# Interface_-_RS485.net
KiCad netlist of a schematic drawn in Altium Designer
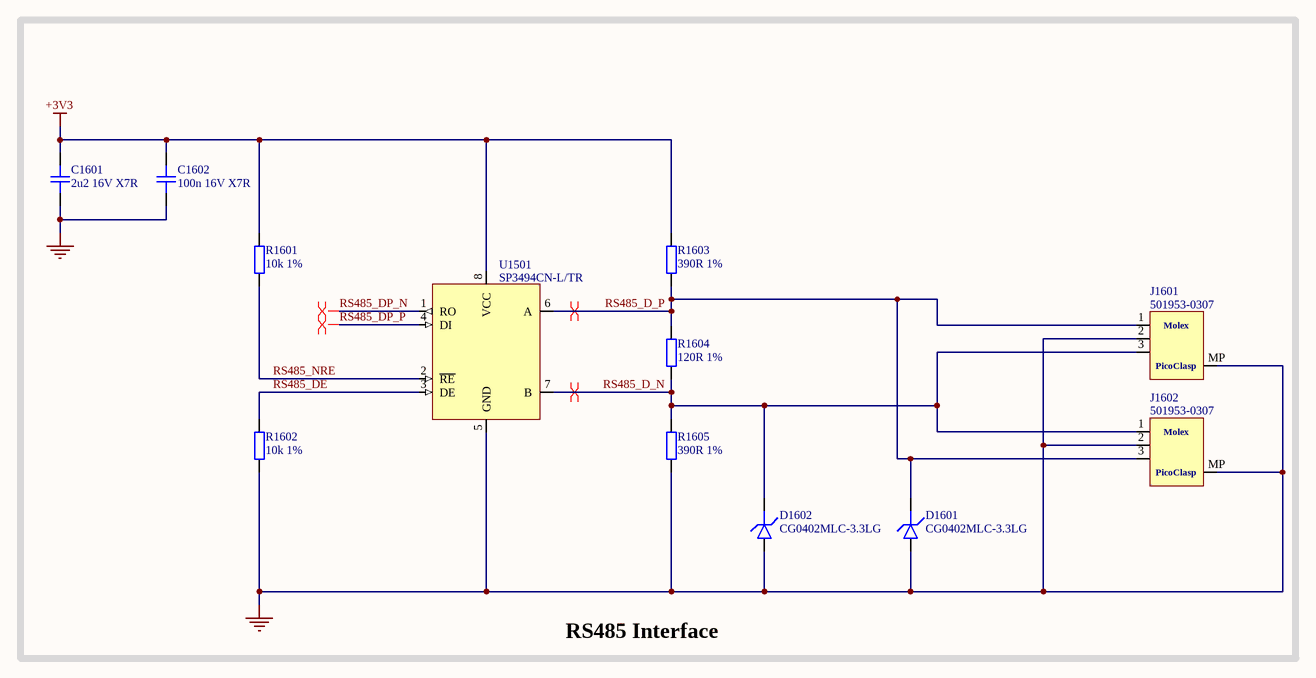
[diagram p0: Interface - RS485.SchDoc]

(export (version "E")
  (design (tool "Eeschema 10.0.6"))
  (components
    (comp (ref "C1601")
      (value "2u2 16V X7R")
      (footprint "CAP_0603")
      (description "Capacitor SMD 0603")
      (fields
        (field (name "MANUFACTURER") "YAGEO")
        (field (name "MANUFACTURER PART NUMBER") "CC0603KRX7R7BB225")
      )
      (libsource (lib "Schematic-Lib-PhilsLab") (part "CAP_0603"))
    )
    (comp (ref "C1602")
      (value "100n 16V X7R")
      (footprint "CAP_0402")
      (description "Capacitor SMD 0402")
      (fields
        (field (name "MANUFACTURER") "YAGEO")
        (field (name "MANUFACTURER PART NUMBER") "CC0402JRX7R7BB104")
      )
      (libsource (lib "Schematic-Lib-PhilsLab") (part "CAP_0402"))
    )
    (comp (ref "D1601")
      (value "CG0402MLC-3.3LG")
      (footprint "D_0402")
      (description "Diode TVS / ESD 0402")
      (libsource (lib "Schematic-Lib-PhilsLab") (part "D_TVS_0402"))
    )
    (comp (ref "D1602")
      (value "CG0402MLC-3.3LG")
      (footprint "D_0402")
      (description "Diode TVS / ESD 0402")
      (libsource (lib "Schematic-Lib-PhilsLab") (part "D_TVS_0402"))
    )
    (comp (ref "J1601")
      (value "501953-0307")
      (footprint "5019530307")
      (description "Headers & Wire Housings 1.0WtBWaferAssyR/A1- -Row3Ckt+LKEmbsTpPkg")
      (libsource (lib "Schematic-Lib-PhilsLab") (part "501953-0307"))
    )
    (comp (ref "J1602")
      (value "501953-0307")
      (footprint "5019530307")
      (description "Headers & Wire Housings 1.0WtBWaferAssyR/A1- -Row3Ckt+LKEmbsTpPkg")
      (libsource (lib "Schematic-Lib-PhilsLab") (part "501953-0307"))
    )
    (comp (ref "R1601")
      (value "10k 1%")
      (footprint "RES_0402")
      (description "Resistor SMD 0402")
      (fields
        (field (name "MANUFACTURER") "PANASONIC")
        (field (name "MANUFACTURER PART NUMBER") "ERJPA2F1002X")
      )
      (libsource (lib "Schematic-Lib-PhilsLab") (part "RES_0402"))
    )
    (comp (ref "R1602")
      (value "10k 1%")
      (footprint "RES_0402")
      (description "Resistor SMD 0402")
      (fields
        (field (name "MANUFACTURER") "PANASONIC")
        (field (name "MANUFACTURER PART NUMBER") "ERJPA2F1002X")
      )
      (libsource (lib "Schematic-Lib-PhilsLab") (part "RES_0402"))
    )
    (comp (ref "R1603")
      (value "390R 1%")
      (footprint "RES_0402")
      (description "Resistor SMD 0402")
      (fields
        (field (name "MANUFACTURER") "PANASONIC")
        (field (name "MANUFACTURER PART NUMBER") "ERJ2GEJ391X")
      )
      (libsource (lib "Schematic-Lib-PhilsLab") (part "RES_0402"))
    )
    (comp (ref "R1604")
      (value "120R 1%")
      (footprint "RES_0402")
      (description "Resistor SMD 0402")
      (fields
        (field (name "MANUFACTURER") "PANASONIC")
        (field (name "MANUFACTURER PART NUMBER") "ERJ2GEJ121X")
      )
      (libsource (lib "Schematic-Lib-PhilsLab") (part "RES_0402"))
    )
    (comp (ref "R1605")
      (value "390R 1%")
      (footprint "RES_0402")
      (description "Resistor SMD 0402")
      (fields
        (field (name "MANUFACTURER") "PANASONIC")
        (field (name "MANUFACTURER PART NUMBER") "ERJ2GEJ391X")
      )
      (libsource (lib "Schematic-Lib-PhilsLab") (part "RES_0402"))
    )
    (comp (ref "U1501")
      (value "SP3494CN-L/TR")
      (footprint "SOIC-8")
      (description "3.3V Low Power RS-485 / RS-422 Transceiver SOIC-8")
      (fields (field (name "MANUFACTURER") "MaxLinear"))
      (libsource (lib "Schematic-Lib-PhilsLab") (part "SP3494CN-L/TR"))
    )
  )
  (nets
    (net (code "1") (name "+3V3") (class "Default")
      (node (ref "C1601") (pin "2") (pinfunction "2_2") (pintype "passive"))
      (node (ref "C1602") (pin "2") (pinfunction "2_2") (pintype "passive"))
      (node (ref "R1601") (pin "2") (pinfunction "2_2") (pintype "passive"))
      (node (ref "R1603") (pin "2") (pinfunction "2_2") (pintype "passive"))
      (node (ref "U1501") (pin "8") (pinfunction "VCC_8") (pintype "power_in"))
    )
    (net (code "2") (name "/RS485_DE") (class "Default")
      (node (ref "R1602") (pin "2") (pinfunction "2_2") (pintype "passive"))
      (node (ref "U1501") (pin "3") (pinfunction "DE_3") (pintype "input"))
    )
    (net (code "3") (name "/RS485_DP_N") (class "Default")
      (node (ref "U1501") (pin "1") (pinfunction "RO_1") (pintype "output"))
    )
    (net (code "4") (name "/RS485_DP_P") (class "Default")
      (node (ref "U1501") (pin "4") (pinfunction "DI_4") (pintype "input"))
    )
    (net (code "5") (name "/RS485_D_N") (class "Default")
      (node (ref "D1602") (pin "K") (pinfunction "K_K") (pintype "passive"))
      (node (ref "J1601") (pin "3") (pinfunction "3_3") (pintype "passive"))
      (node (ref "J1602") (pin "1") (pinfunction "1_1") (pintype "passive"))
      (node (ref "R1604") (pin "1") (pinfunction "1_1") (pintype "passive"))
      (node (ref "R1605") (pin "2") (pinfunction "2_2") (pintype "passive"))
      (node (ref "U1501") (pin "7") (pinfunction "B_7") (pintype "bidirectional"))
    )
    (net (code "6") (name "/RS485_D_P") (class "Default")
      (node (ref "D1601") (pin "K") (pinfunction "K_K") (pintype "passive"))
      (node (ref "J1601") (pin "1") (pinfunction "1_1") (pintype "passive"))
      (node (ref "J1602") (pin "3") (pinfunction "3_3") (pintype "passive"))
      (node (ref "R1603") (pin "1") (pinfunction "1_1") (pintype "passive"))
      (node (ref "R1604") (pin "2") (pinfunction "2_2") (pintype "passive"))
      (node (ref "U1501") (pin "6") (pinfunction "A_6") (pintype "bidirectional"))
    )
    (net (code "7") (name "/RS485_NRE") (class "Default")
      (node (ref "R1601") (pin "1") (pinfunction "1_1") (pintype "passive"))
      (node (ref "U1501") (pin "2") (pinfunction "~{RE}_2") (pintype "input"))
    )
    (net (code "8") (name "GND") (class "Default")
      (node (ref "C1601") (pin "1") (pinfunction "1_1") (pintype "passive"))
      (node (ref "C1602") (pin "1") (pinfunction "1_1") (pintype "passive"))
      (node (ref "D1601") (pin "A") (pinfunction "A_A") (pintype "passive"))
      (node (ref "D1602") (pin "A") (pinfunction "A_A") (pintype "passive"))
      (node (ref "J1601") (pin "2") (pinfunction "2_2") (pintype "passive"))
      (node (ref "J1601") (pin "MP") (pinfunction "MP_MP") (pintype "passive"))
      (node (ref "J1602") (pin "2") (pinfunction "2_2") (pintype "passive"))
      (node (ref "J1602") (pin "MP") (pinfunction "MP_MP") (pintype "passive"))
      (node (ref "R1602") (pin "1") (pinfunction "1_1") (pintype "passive"))
      (node (ref "R1605") (pin "1") (pinfunction "1_1") (pintype "passive"))
      (node (ref "U1501") (pin "5") (pinfunction "GND_5") (pintype "power_in"))
    )
  )
)
